# pr0board.net
KiCad netlist of a schematic drawn in EAGLE
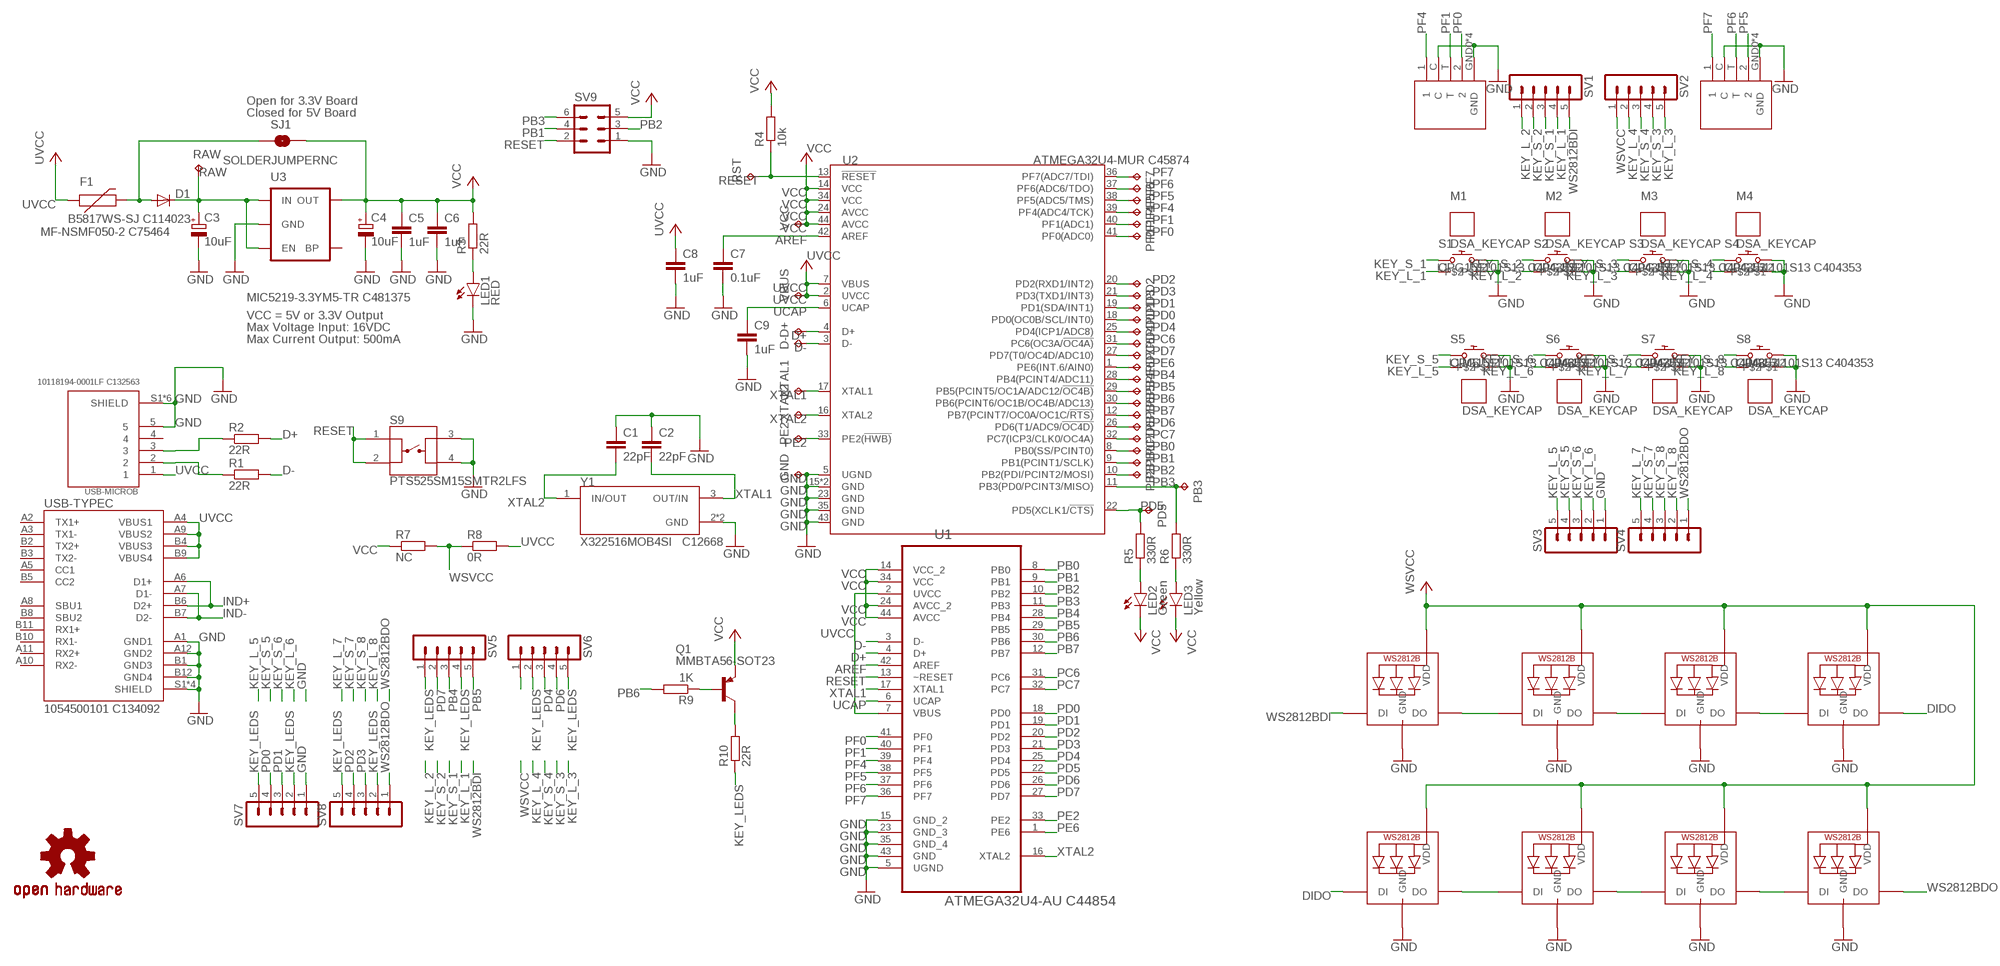
[diagram p0: schematic, sheet 1]

(export (version "E")
  (design (tool "Eeschema 10.0.6"))
  (components
    (comp (ref "C1")
      (value "22pF")
      (footprint "eagle-import:C0603")
      (libsource (lib "eagle-import") (part "C-EUC0603"))
    )
    (comp (ref "C2")
      (value "22pF")
      (footprint "eagle-import:C0603")
      (libsource (lib "eagle-import") (part "C-EUC0603"))
    )
    (comp (ref "C3")
      (value "10uF")
      (footprint "eagle-import:CT3216")
      (libsource (lib "eagle-import") (part "CPOL-EUCT3216"))
    )
    (comp (ref "C4")
      (value "10uF")
      (footprint "eagle-import:CT3216")
      (libsource (lib "eagle-import") (part "CPOL-EUCT3216"))
    )
    (comp (ref "C5")
      (value "1uF")
      (footprint "eagle-import:C0603")
      (libsource (lib "eagle-import") (part "C-EUC0603"))
    )
    (comp (ref "C6")
      (value "1uF")
      (footprint "eagle-import:C0603")
      (libsource (lib "eagle-import") (part "C-EUC0603"))
    )
    (comp (ref "C7")
      (value "0.1uF")
      (footprint "eagle-import:C0603")
      (libsource (lib "eagle-import") (part "C-EUC0603"))
    )
    (comp (ref "C8")
      (value "1uF")
      (footprint "eagle-import:C0603")
      (libsource (lib "eagle-import") (part "C-EUC0603"))
    )
    (comp (ref "C9")
      (value "1uF")
      (footprint "eagle-import:C0603")
      (libsource (lib "eagle-import") (part "C-EUC0603"))
    )
    (comp (ref "D+")
      (value "TPB1,27")
      (footprint "eagle-import:B1,27")
      (libsource (lib "eagle-import") (part "TPB1,27"))
    )
    (comp (ref "D-")
      (value "TPB1,27")
      (footprint "eagle-import:B1,27")
      (libsource (lib "eagle-import") (part "TPB1,27"))
    )
    (comp (ref "D1")
      (value "B5817WS-SJ C114023")
      (footprint "eagle-import:SOD-323")
      (libsource (lib "eagle-import") (part "DIODESOD"))
    )
    (comp (ref "F1")
      (value "MF-NSMF050-2 C75464")
      (footprint "eagle-import:PTC-1206")
      (libsource (lib "eagle-import") (part "PTCSMD"))
    )
    (comp (ref "GND")
      (value "TPB1,27")
      (footprint "eagle-import:B1,27")
      (libsource (lib "eagle-import") (part "TPB1,27"))
    )
    (comp (ref "LED1")
      (value "RED")
      (footprint "eagle-import:CHIP-LED0603")
      (libsource (lib "eagle-import") (part "LEDCHIP-LED0603"))
    )
    (comp (ref "LED2")
      (value "Green")
      (footprint "eagle-import:CHIP-LED0603")
      (libsource (lib "eagle-import") (part "LEDCHIP-LED0603"))
    )
    (comp (ref "LED3")
      (value "Yellow")
      (footprint "eagle-import:CHIP-LED0603")
      (libsource (lib "eagle-import") (part "LEDCHIP-LED0603"))
    )
    (comp (ref "LED4")
      (value "WS2812B3535")
      (footprint "eagle-import:LED3535")
      (libsource (lib "eagle-import") (part "WS2812B3535"))
    )
    (comp (ref "LED5")
      (value "WS2812B3535")
      (footprint "eagle-import:LED3535")
      (libsource (lib "eagle-import") (part "WS2812B3535"))
    )
    (comp (ref "LED6")
      (value "WS2812B3535")
      (footprint "eagle-import:LED3535")
      (libsource (lib "eagle-import") (part "WS2812B3535"))
    )
    (comp (ref "LED7")
      (value "WS2812B3535")
      (footprint "eagle-import:LED3535")
      (libsource (lib "eagle-import") (part "WS2812B3535"))
    )
    (comp (ref "LED8")
      (value "WS2812B3535")
      (footprint "eagle-import:LED3535")
      (libsource (lib "eagle-import") (part "WS2812B3535"))
    )
    (comp (ref "LED9")
      (value "WS2812B3535")
      (footprint "eagle-import:LED3535")
      (libsource (lib "eagle-import") (part "WS2812B3535"))
    )
    (comp (ref "LED10")
      (value "WS2812B3535")
      (footprint "eagle-import:LED3535")
      (libsource (lib "eagle-import") (part "WS2812B3535"))
    )
    (comp (ref "LED11")
      (value "WS2812B3535")
      (footprint "eagle-import:LED3535")
      (libsource (lib "eagle-import") (part "WS2812B3535"))
    )
    (comp (ref "M1")
      (value "DSA_KEYCAP")
      (footprint "eagle-import:DSA_KEYCAP")
      (libsource (lib "eagle-import") (part "DSA_KEYCAP"))
    )
    (comp (ref "M2")
      (value "DSA_KEYCAP")
      (footprint "eagle-import:DSA_KEYCAP")
      (libsource (lib "eagle-import") (part "DSA_KEYCAP"))
    )
    (comp (ref "M3")
      (value "DSA_KEYCAP")
      (footprint "eagle-import:DSA_KEYCAP")
      (libsource (lib "eagle-import") (part "DSA_KEYCAP"))
    )
    (comp (ref "M4")
      (value "DSA_KEYCAP")
      (footprint "eagle-import:DSA_KEYCAP")
      (libsource (lib "eagle-import") (part "DSA_KEYCAP"))
    )
    (comp (ref "M5")
      (value "DSA_KEYCAP")
      (footprint "eagle-import:DSA_KEYCAP")
      (libsource (lib "eagle-import") (part "DSA_KEYCAP"))
    )
    (comp (ref "M6")
      (value "DSA_KEYCAP")
      (footprint "eagle-import:DSA_KEYCAP")
      (libsource (lib "eagle-import") (part "DSA_KEYCAP"))
    )
    (comp (ref "M7")
      (value "DSA_KEYCAP")
      (footprint "eagle-import:DSA_KEYCAP")
      (libsource (lib "eagle-import") (part "DSA_KEYCAP"))
    )
    (comp (ref "M8")
      (value "DSA_KEYCAP")
      (footprint "eagle-import:DSA_KEYCAP")
      (libsource (lib "eagle-import") (part "DSA_KEYCAP"))
    )
    (comp (ref "PB0")
      (value "TPB1,27")
      (footprint "eagle-import:B1,27")
      (libsource (lib "eagle-import") (part "TPB1,27"))
    )
    (comp (ref "PB1")
      (value "TPB1,27")
      (footprint "eagle-import:B1,27")
      (libsource (lib "eagle-import") (part "TPB1,27"))
    )
    (comp (ref "PB2")
      (value "TPB1,27")
      (footprint "eagle-import:B1,27")
      (libsource (lib "eagle-import") (part "TPB1,27"))
    )
    (comp (ref "PB3")
      (value "TPB1,27")
      (footprint "eagle-import:B1,27")
      (libsource (lib "eagle-import") (part "TPB1,27"))
    )
    (comp (ref "PB4")
      (value "TPB1,27")
      (footprint "eagle-import:B1,27")
      (libsource (lib "eagle-import") (part "TPB1,27"))
    )
    (comp (ref "PB5")
      (value "TPB1,27")
      (footprint "eagle-import:B1,27")
      (libsource (lib "eagle-import") (part "TPB1,27"))
    )
    (comp (ref "PB6")
      (value "TPB1,27")
      (footprint "eagle-import:B1,27")
      (libsource (lib "eagle-import") (part "TPB1,27"))
    )
    (comp (ref "PB7")
      (value "TPB1,27")
      (footprint "eagle-import:B1,27")
      (libsource (lib "eagle-import") (part "TPB1,27"))
    )
    (comp (ref "PC6")
      (value "TPB1,27")
      (footprint "eagle-import:B1,27")
      (libsource (lib "eagle-import") (part "TPB1,27"))
    )
    (comp (ref "PC7")
      (value "TPB1,27")
      (footprint "eagle-import:B1,27")
      (libsource (lib "eagle-import") (part "TPB1,27"))
    )
    (comp (ref "PD0")
      (value "TPB1,27")
      (footprint "eagle-import:B1,27")
      (libsource (lib "eagle-import") (part "TPB1,27"))
    )
    (comp (ref "PD1")
      (value "TPB1,27")
      (footprint "eagle-import:B1,27")
      (libsource (lib "eagle-import") (part "TPB1,27"))
    )
    (comp (ref "PD2")
      (value "TPB1,27")
      (footprint "eagle-import:B1,27")
      (libsource (lib "eagle-import") (part "TPB1,27"))
    )
    (comp (ref "PD3")
      (value "TPB1,27")
      (footprint "eagle-import:B1,27")
      (libsource (lib "eagle-import") (part "TPB1,27"))
    )
    (comp (ref "PD4")
      (value "TPB1,27")
      (footprint "eagle-import:B1,27")
      (libsource (lib "eagle-import") (part "TPB1,27"))
    )
    (comp (ref "PD5")
      (value "TPB1,27")
      (footprint "eagle-import:B1,27")
      (libsource (lib "eagle-import") (part "TPB1,27"))
    )
    (comp (ref "PD6")
      (value "TPB1,27")
      (footprint "eagle-import:B1,27")
      (libsource (lib "eagle-import") (part "TPB1,27"))
    )
    (comp (ref "PD7")
      (value "TPB1,27")
      (footprint "eagle-import:B1,27")
      (libsource (lib "eagle-import") (part "TPB1,27"))
    )
    (comp (ref "PE2")
      (value "TPB1,27")
      (footprint "eagle-import:B1,27")
      (libsource (lib "eagle-import") (part "TPB1,27"))
    )
    (comp (ref "PE6")
      (value "TPB1,27")
      (footprint "eagle-import:B1,27")
      (libsource (lib "eagle-import") (part "TPB1,27"))
    )
    (comp (ref "PF0")
      (value "TPB1,27")
      (footprint "eagle-import:B1,27")
      (libsource (lib "eagle-import") (part "TPB1,27"))
    )
    (comp (ref "PF1")
      (value "TPB1,27")
      (footprint "eagle-import:B1,27")
      (libsource (lib "eagle-import") (part "TPB1,27"))
    )
    (comp (ref "PF4")
      (value "TPB1,27")
      (footprint "eagle-import:B1,27")
      (libsource (lib "eagle-import") (part "TPB1,27"))
    )
    (comp (ref "PF5")
      (value "TPB1,27")
      (footprint "eagle-import:B1,27")
      (libsource (lib "eagle-import") (part "TPB1,27"))
    )
    (comp (ref "PF6")
      (value "TPB1,27")
      (footprint "eagle-import:B1,27")
      (libsource (lib "eagle-import") (part "TPB1,27"))
    )
    (comp (ref "PF7")
      (value "TPB1,27")
      (footprint "eagle-import:B1,27")
      (libsource (lib "eagle-import") (part "TPB1,27"))
    )
    (comp (ref "Q1")
      (value "MMBTA56-SOT23")
      (footprint "eagle-import:SOT23")
      (libsource (lib "eagle-import") (part "-?SOT23MMBTA56"))
    )
    (comp (ref "R1")
      (value "22R")
      (footprint "eagle-import:R0603")
      (libsource (lib "eagle-import") (part "resistor_348_R-EU_R0603"))
    )
    (comp (ref "R2")
      (value "22R")
      (footprint "eagle-import:R0603")
      (libsource (lib "eagle-import") (part "resistor_348_R-EU_R0603"))
    )
    (comp (ref "R3")
      (value "22R")
      (footprint "eagle-import:R0603")
      (libsource (lib "eagle-import") (part "resistor_348_R-EU_R0603"))
    )
    (comp (ref "R4")
      (value "10k")
      (footprint "eagle-import:R0603")
      (libsource (lib "eagle-import") (part "resistor_348_R-EU_R0603"))
    )
    (comp (ref "R5")
      (value "330R")
      (footprint "eagle-import:R0603")
      (libsource (lib "eagle-import") (part "resistor_348_R-EU_R0603"))
    )
    (comp (ref "R6")
      (value "330R")
      (footprint "eagle-import:R0603")
      (libsource (lib "eagle-import") (part "resistor_348_R-EU_R0603"))
    )
    (comp (ref "R7")
      (value "NC")
      (footprint "eagle-import:R0603")
      (libsource (lib "eagle-import") (part "resistor_348_R-EU_R0603"))
    )
    (comp (ref "R8")
      (value "0R")
      (footprint "eagle-import:R0603")
      (libsource (lib "eagle-import") (part "resistor_348_R-EU_R0603"))
    )
    (comp (ref "R9")
      (value "1K")
      (footprint "eagle-import:R0603")
      (libsource (lib "eagle-import") (part "R-EU_R0603"))
    )
    (comp (ref "R10")
      (value "22R")
      (footprint "eagle-import:R0805")
      (libsource (lib "eagle-import") (part "R-EU_R0805"))
    )
    (comp (ref "RAW")
      (value "TPB1,27")
      (footprint "eagle-import:B1,27")
      (libsource (lib "eagle-import") (part "TPB1,27"))
    )
    (comp (ref "RST")
      (value "TPB1,27")
      (footprint "eagle-import:B1,27")
      (libsource (lib "eagle-import") (part "TPB1,27"))
    )
    (comp (ref "S1")
      (value "CPG151101S13 C404353")
      (footprint "eagle-import:CHERRY_MX_LED")
      (libsource (lib "eagle-import") (part "CHERRY_MX_LED"))
    )
    (comp (ref "S2")
      (value "CPG151101S13 C404353")
      (footprint "eagle-import:CHERRY_MX_LED")
      (libsource (lib "eagle-import") (part "CHERRY_MX_LED"))
    )
    (comp (ref "S3")
      (value "CPG151101S13 C404353")
      (footprint "eagle-import:CHERRY_MX_LED")
      (libsource (lib "eagle-import") (part "CHERRY_MX_LED"))
    )
    (comp (ref "S4")
      (value "CPG151101S13 C404353")
      (footprint "eagle-import:CHERRY_MX_LED")
      (libsource (lib "eagle-import") (part "CHERRY_MX_LED"))
    )
    (comp (ref "S5")
      (value "CPG151101S13 C404353")
      (footprint "eagle-import:CHERRY_MX_LED")
      (libsource (lib "eagle-import") (part "CHERRY_MX_LED"))
    )
    (comp (ref "S6")
      (value "CPG151101S13 C404353")
      (footprint "eagle-import:CHERRY_MX_LED")
      (libsource (lib "eagle-import") (part "CHERRY_MX_LED"))
    )
    (comp (ref "S7")
      (value "CPG151101S13 C404353")
      (footprint "eagle-import:CHERRY_MX_LED")
      (libsource (lib "eagle-import") (part "CHERRY_MX_LED"))
    )
    (comp (ref "S8")
      (value "CPG151101S13 C404353")
      (footprint "eagle-import:CHERRY_MX_LED")
      (libsource (lib "eagle-import") (part "CHERRY_MX_LED"))
    )
    (comp (ref "S9")
      (value "PTS525SM15SMTR2LFS")
      (footprint "eagle-import:SW_PTS525SM15SMTR2LFS")
      (fields (field (name "MF") "C&K"))
      (libsource (lib "eagle-import") (part "PTS525SM15SMTR2LFS"))
    )
    (comp (ref "SJ1")
      (value "SOLDERJUMPERNC")
      (footprint "eagle-import:SJ_2S")
      (libsource (lib "eagle-import") (part "SOLDERJUMPERNC"))
    )
    (comp (ref "SV1")
      (value "MA05-1")
      (footprint "eagle-import:MA05-1")
      (libsource (lib "eagle-import") (part "MA05-1"))
    )
    (comp (ref "SV2")
      (value "MA05-1")
      (footprint "eagle-import:MA05-1")
      (libsource (lib "eagle-import") (part "MA05-1"))
    )
    (comp (ref "SV3")
      (value "MA05-1")
      (footprint "eagle-import:MA05-1")
      (libsource (lib "eagle-import") (part "MA05-1"))
    )
    (comp (ref "SV4")
      (value "MA05-1")
      (footprint "eagle-import:MA05-1")
      (libsource (lib "eagle-import") (part "MA05-1"))
    )
    (comp (ref "SV5")
      (value "MA05-1")
      (footprint "eagle-import:MA05-1")
      (libsource (lib "eagle-import") (part "MA05-1"))
    )
    (comp (ref "SV6")
      (value "MA05-1")
      (footprint "eagle-import:MA05-1")
      (libsource (lib "eagle-import") (part "MA05-1"))
    )
    (comp (ref "SV7")
      (value "MA05-1")
      (footprint "eagle-import:MA05-1")
      (libsource (lib "eagle-import") (part "MA05-1"))
    )
    (comp (ref "SV8")
      (value "MA05-1")
      (footprint "eagle-import:MA05-1")
      (libsource (lib "eagle-import") (part "MA05-1"))
    )
    (comp (ref "SV9")
      (value "MA03-2")
      (footprint "eagle-import:MA03-2")
      (libsource (lib "eagle-import") (part "MA03-2"))
    )
    (comp (ref "U$1")
      (value "OSHW-LOGOS")
      (footprint "eagle-import:OSHW-LOGO-S")
      (libsource (lib "eagle-import") (part "OSHW-LOGOS"))
    )
    (comp (ref "U$2")
      (value "TM-2024A")
      (footprint "eagle-import:TM-2024A")
      (libsource (lib "eagle-import") (part "TM-2024A"))
    )
    (comp (ref "U$3")
      (value "TM-2024A")
      (footprint "eagle-import:TM-2024A")
      (libsource (lib "eagle-import") (part "TM-2024A"))
    )
    (comp (ref "U1")
      (value "ATMEGA32U4-AU C44854")
      (footprint "eagle-import:QFP80P1200X1200X120-44N")
      (fields (field (name "MF") "Microchip Technology") (field (name "MP") "ATMEGA32U4-AU"))
      (libsource (lib "eagle-import") (part "ATMEGA32U4-AU"))
    )
    (comp (ref "U2")
      (value "ATMEGA32U4-MUR C45874")
      (footprint "eagle-import:QFN44G-0.5-7X7MM")
      (fields (field (name "MF") "Microchip") (field (name "MP") "ATMEGA32U4-MUR"))
      (libsource (lib "eagle-import") (part "MCU-ATMEGA32U4-MUR(VQFN44)"))
    )
    (comp (ref "U3")
      (value "MIC5219-3.3YM5-TR C481375")
      (footprint "eagle-import:SC70")
      (libsource (lib "eagle-import") (part "V_REG_LDOSMD2"))
    )
    (comp (ref "USB-MICROB")
      (value "10118194-0001LF C132563")
      (footprint "eagle-import:AMPHENOL_10118194-0001LF")
      (fields (field (name "MF") "Amphenol ICC (FCI)") (field (name "MP") "10118194-0001LF"))
      (libsource (lib "eagle-import") (part "10118194-0001LF"))
    )
    (comp (ref "USB-TYPEC")
      (value "1054500101 C134092")
      (footprint "eagle-import:MOLEX_105450-0101")
      (fields (field (name "MF") "Molex") (field (name "MP") "1054500101"))
      (libsource (lib "eagle-import") (part "105450-0101"))
    )
    (comp (ref "VBUS")
      (value "TPB1,27")
      (footprint "eagle-import:B1,27")
      (libsource (lib "eagle-import") (part "TPB1,27"))
    )
    (comp (ref "VCC")
      (value "TPB1,27")
      (footprint "eagle-import:B1,27")
      (libsource (lib "eagle-import") (part "TPB1,27"))
    )
    (comp (ref "XTAL1")
      (value "TPB1,27")
      (footprint "eagle-import:B1,27")
      (libsource (lib "eagle-import") (part "TPB1,27"))
    )
    (comp (ref "XTAL2")
      (value "TPB1,27")
      (footprint "eagle-import:B1,27")
      (libsource (lib "eagle-import") (part "TPB1,27"))
    )
    (comp (ref "Y1")
      (value "X322516MOB4SI C12668")
      (footprint "eagle-import:XTAL_ECS-160-18-33Q-DS")
      (fields (field (name "MF") "ECS Inc.") (field (name "MP") "ECS-160-18-33Q-DS"))
      (libsource (lib "eagle-import") (part "ECS-160-18-33Q-DS"))
    )
  )
  (nets
    (net (code "1") (name "/AREF") (class "Default")
      (node (ref "C7") (pin "1") (pinfunction "1_1") (pintype "passive"))
      (node (ref "U1") (pin "42") (pinfunction "AREF_42") (pintype "input"))
      (node (ref "U2") (pin "42") (pinfunction "AREF_42") (pintype "bidirectional"))
    )
    (net (code "2") (name "/D+") (class "Default")
      (node (ref "D+") (pin "TP") (pinfunction "TP_TP") (pintype "input"))
      (node (ref "R2") (pin "2") (pinfunction "2_2") (pintype "passive"))
      (node (ref "U1") (pin "4") (pinfunction "D+_4") (pintype "passive"))
      (node (ref "U2") (pin "4") (pinfunction "D+_4") (pintype "bidirectional"))
    )
    (net (code "3") (name "/D-") (class "Default")
      (node (ref "D-") (pin "TP") (pinfunction "TP_TP") (pintype "input"))
      (node (ref "R1") (pin "2") (pinfunction "2_2") (pintype "passive"))
      (node (ref "U1") (pin "3") (pinfunction "D-_3") (pintype "passive"))
      (node (ref "U2") (pin "3") (pinfunction "D-_3") (pintype "bidirectional"))
    )
    (net (code "4") (name "/DIDO") (class "Default")
      (node (ref "LED7") (pin "3") (pinfunction "DO_3") (pintype "output"))
      (node (ref "LED8") (pin "1") (pinfunction "DI_1") (pintype "input"))
    )
    (net (code "5") (name "/IND+") (class "Default")
      (node (ref "R2") (pin "1") (pinfunction "1_1") (pintype "passive"))
      (node (ref "USB-MICROB") (pin "3") (pinfunction "3_3") (pintype "passive"))
      (node (ref "USB-TYPEC") (pin "A6") (pinfunction "D1+_A6") (pintype "passive"))
      (node (ref "USB-TYPEC") (pin "B6") (pinfunction "D2+_B6") (pintype "passive"))
    )
    (net (code "6") (name "/IND-") (class "Default")
      (node (ref "R1") (pin "1") (pinfunction "1_1") (pintype "passive"))
      (node (ref "USB-MICROB") (pin "2") (pinfunction "2_2") (pintype "passive"))
      (node (ref "USB-TYPEC") (pin "A7") (pinfunction "D1-_A7") (pintype "passive"))
      (node (ref "USB-TYPEC") (pin "B7") (pinfunction "D2-_B7") (pintype "passive"))
    )
    (net (code "7") (name "/KEY_LEDS") (class "Default")
      (node (ref "R10") (pin "1") (pinfunction "1_1") (pintype "passive"))
      (node (ref "SV5") (pin "1") (pinfunction "1_1") (pintype "passive"))
      (node (ref "SV5") (pin "4") (pinfunction "4_4") (pintype "passive"))
      (node (ref "SV6") (pin "2") (pinfunction "2_2") (pintype "passive"))
      (node (ref "SV6") (pin "5") (pinfunction "5_5") (pintype "passive"))
      (node (ref "SV7") (pin "2") (pinfunction "2_2") (pintype "passive"))
      (node (ref "SV7") (pin "5") (pinfunction "5_5") (pintype "passive"))
      (node (ref "SV8") (pin "2") (pinfunction "2_2") (pintype "passive"))
      (node (ref "SV8") (pin "5") (pinfunction "5_5") (pintype "passive"))
    )
    (net (code "8") (name "/KEY_L_1") (class "Default")
      (node (ref "S1") (pin "L1") (pinfunction "P$1_L1") (pintype "bidirectional"))
      (node (ref "SV1") (pin "4") (pinfunction "4_4") (pintype "passive"))
    )
    (net (code "9") (name "/KEY_L_2") (class "Default")
      (node (ref "S2") (pin "L1") (pinfunction "P$1_L1") (pintype "bidirectional"))
      (node (ref "SV1") (pin "1") (pinfunction "1_1") (pintype "passive"))
    )
    (net (code "10") (name "/KEY_L_3") (class "Default")
      (node (ref "S3") (pin "L1") (pinfunction "P$1_L1") (pintype "bidirectional"))
      (node (ref "SV2") (pin "5") (pinfunction "5_5") (pintype "passive"))
    )
    (net (code "11") (name "/KEY_L_4") (class "Default")
      (node (ref "S4") (pin "L1") (pinfunction "P$1_L1") (pintype "bidirectional"))
      (node (ref "SV2") (pin "2") (pinfunction "2_2") (pintype "passive"))
    )
    (net (code "12") (name "/KEY_L_5") (class "Default")
      (node (ref "S5") (pin "L1") (pinfunction "P$1_L1") (pintype "bidirectional"))
      (node (ref "SV3") (pin "5") (pinfunction "5_5") (pintype "passive"))
    )
    (net (code "13") (name "/KEY_L_6") (class "Default")
      (node (ref "S6") (pin "L1") (pinfunction "P$1_L1") (pintype "bidirectional"))
      (node (ref "SV3") (pin "2") (pinfunction "2_2") (pintype "passive"))
    )
    (net (code "14") (name "/KEY_L_7") (class "Default")
      (node (ref "S7") (pin "L1") (pinfunction "P$1_L1") (pintype "bidirectional"))
      (node (ref "SV4") (pin "5") (pinfunction "5_5") (pintype "passive"))
    )
    (net (code "15") (name "/KEY_L_8") (class "Default")
      (node (ref "S8") (pin "L1") (pinfunction "P$1_L1") (pintype "bidirectional"))
      (node (ref "SV4") (pin "2") (pinfunction "2_2") (pintype "passive"))
    )
    (net (code "16") (name "/KEY_S_1") (class "Default")
      (node (ref "S1") (pin "S1") (pinfunction "1_S1") (pintype "passive"))
      (node (ref "SV1") (pin "3") (pinfunction "3_3") (pintype "passive"))
    )
    (net (code "17") (name "/KEY_S_2") (class "Default")
      (node (ref "S2") (pin "S1") (pinfunction "1_S1") (pintype "passive"))
      (node (ref "SV1") (pin "2") (pinfunction "2_2") (pintype "passive"))
    )
    (net (code "18") (name "/KEY_S_3") (class "Default")
      (node (ref "S3") (pin "S1") (pinfunction "1_S1") (pintype "passive"))
      (node (ref "SV2") (pin "4") (pinfunction "4_4") (pintype "passive"))
    )
    (net (code "19") (name "/KEY_S_4") (class "Default")
      (node (ref "S4") (pin "S1") (pinfunction "1_S1") (pintype "passive"))
      (node (ref "SV2") (pin "3") (pinfunction "3_3") (pintype "passive"))
    )
    (net (code "20") (name "/KEY_S_5") (class "Default")
      (node (ref "S5") (pin "S1") (pinfunction "1_S1") (pintype "passive"))
      (node (ref "SV3") (pin "4") (pinfunction "4_4") (pintype "passive"))
    )
    (net (code "21") (name "/KEY_S_6") (class "Default")
      (node (ref "S6") (pin "S1") (pinfunction "1_S1") (pintype "passive"))
      (node (ref "SV3") (pin "3") (pinfunction "3_3") (pintype "passive"))
    )
    (net (code "22") (name "/KEY_S_7") (class "Default")
      (node (ref "S7") (pin "S1") (pinfunction "1_S1") (pintype "passive"))
      (node (ref "SV4") (pin "4") (pinfunction "4_4") (pintype "passive"))
    )
    (net (code "23") (name "/KEY_S_8") (class "Default")
      (node (ref "S8") (pin "S1") (pinfunction "1_S1") (pintype "passive"))
      (node (ref "SV4") (pin "3") (pinfunction "3_3") (pintype "passive"))
    )
    (net (code "24") (name "/PB0") (class "Default")
      (node (ref "PB0") (pin "TP") (pinfunction "TP_TP") (pintype "input"))
      (node (ref "U1") (pin "8") (pinfunction "PB0_8") (pintype "bidirectional"))
      (node (ref "U2") (pin "8") (pinfunction "PB0(SS/PCINT0)_8") (pintype "bidirectional"))
    )
    (net (code "25") (name "/PB1") (class "Default")
      (node (ref "PB1") (pin "TP") (pinfunction "TP_TP") (pintype "input"))
      (node (ref "SV9") (pin "4") (pinfunction "4_4") (pintype "passive"))
      (node (ref "U1") (pin "9") (pinfunction "PB1_9") (pintype "bidirectional"))
      (node (ref "U2") (pin "9") (pinfunction "PB1(PCINT1/SCLK)_9") (pintype "bidirectional"))
    )
    (net (code "26") (name "/PB2") (class "Default")
      (node (ref "PB2") (pin "TP") (pinfunction "TP_TP") (pintype "input"))
      (node (ref "SV9") (pin "3") (pinfunction "3_3") (pintype "passive"))
      (node (ref "U1") (pin "10") (pinfunction "PB2_10") (pintype "bidirectional"))
      (node (ref "U2") (pin "10") (pinfunction "PB2(PDI/PCINT2/MOSI)_10") (pintype "bidirectional"))
    )
    (net (code "27") (name "/PB3") (class "Default")
      (node (ref "PB3") (pin "TP") (pinfunction "TP_TP") (pintype "input"))
      (node (ref "R6") (pin "2") (pinfunction "2_2") (pintype "passive"))
      (node (ref "SV9") (pin "6") (pinfunction "6_6") (pintype "passive"))
      (node (ref "U1") (pin "11") (pinfunction "PB3_11") (pintype "bidirectional"))
      (node (ref "U2") (pin "11") (pinfunction "PB3(PD0/PCINT3/MISO)_11") (pintype "bidirectional"))
    )
    (net (code "28") (name "/PB4") (class "Default")
      (node (ref "PB4") (pin "TP") (pinfunction "TP_TP") (pintype "input"))
      (node (ref "SV5") (pin "3") (pinfunction "3_3") (pintype "passive"))
      (node (ref "U1") (pin "28") (pinfunction "PB4_28") (pintype "bidirectional"))
      (node (ref "U2") (pin "28") (pinfunction "PB4(PCINT4/ADC11)_28") (pintype "bidirectional"))
    )
    (net (code "29") (name "/PB5") (class "Default")
      (node (ref "PB5") (pin "TP") (pinfunction "TP_TP") (pintype "input"))
      (node (ref "SV5") (pin "5") (pinfunction "5_5") (pintype "passive"))
      (node (ref "U1") (pin "29") (pinfunction "PB5_29") (pintype "bidirectional"))
      (node (ref "U2") (pin "29") (pinfunction "PB5(PCINT5/OC1A/ADC12/~{OC4B})_29") (pintype "bidirectional"))
    )
    (net (code "30") (name "/PB6") (class "Default")
      (node (ref "PB6") (pin "TP") (pinfunction "TP_TP") (pintype "input"))
      (node (ref "R9") (pin "2") (pinfunction "2_2") (pintype "passive"))
      (node (ref "U1") (pin "30") (pinfunction "PB6_30") (pintype "bidirectional"))
      (node (ref "U2") (pin "30") (pinfunction "PB6(PCINT6/OC1B/OC4B/ADC13)_30") (pintype "bidirectional"))
    )
    (net (code "31") (name "/PB7") (class "Default")
      (node (ref "PB7") (pin "TP") (pinfunction "TP_TP") (pintype "input"))
      (node (ref "U1") (pin "12") (pinfunction "PB7_12") (pintype "bidirectional"))
      (node (ref "U2") (pin "12") (pinfunction "PB7(PCINT7/OC0A/OC1C/~{RTS})_12") (pintype "bidirectional"))
    )
    (net (code "32") (name "/PC6") (class "Default")
      (node (ref "PC6") (pin "TP") (pinfunction "TP_TP") (pintype "input"))
      (node (ref "U1") (pin "31") (pinfunction "PC6_31") (pintype "bidirectional"))
      (node (ref "U2") (pin "31") (pinfunction "PC6(OC3A/~{OC4A})_31") (pintype "bidirectional"))
    )
    (net (code "33") (name "/PC7") (class "Default")
      (node (ref "PC7") (pin "TP") (pinfunction "TP_TP") (pintype "input"))
      (node (ref "U1") (pin "32") (pinfunction "PC7_32") (pintype "bidirectional"))
      (node (ref "U2") (pin "32") (pinfunction "PC7(ICP3/CLK0/OC4A)_32") (pintype "bidirectional"))
    )
    (net (code "34") (name "/PD0") (class "Default")
      (node (ref "PD0") (pin "TP") (pinfunction "TP_TP") (pintype "input"))
      (node (ref "SV7") (pin "4") (pinfunction "4_4") (pintype "passive"))
      (node (ref "U1") (pin "18") (pinfunction "PD0_18") (pintype "bidirectional"))
      (node (ref "U2") (pin "18") (pinfunction "PD0(OC0B/SCL/INT0)_18") (pintype "bidirectional"))
    )
    (net (code "35") (name "/PD1") (class "Default")
      (node (ref "PD1") (pin "TP") (pinfunction "TP_TP") (pintype "input"))
      (node (ref "SV7") (pin "3") (pinfunction "3_3") (pintype "passive"))
      (node (ref "U1") (pin "19") (pinfunction "PD1_19") (pintype "bidirectional"))
      (node (ref "U2") (pin "19") (pinfunction "PD1(SDA/INT1)_19") (pintype "bidirectional"))
    )
    (net (code "36") (name "/PD2") (class "Default")
      (node (ref "PD2") (pin "TP") (pinfunction "TP_TP") (pintype "input"))
      (node (ref "SV8") (pin "4") (pinfunction "4_4") (pintype "passive"))
      (node (ref "U1") (pin "20") (pinfunction "PD2_20") (pintype "bidirectional"))
      (node (ref "U2") (pin "20") (pinfunction "PD2(RXD1/INT2)_20") (pintype "bidirectional"))
    )
    (net (code "37") (name "/PD3") (class "Default")
      (node (ref "PD3") (pin "TP") (pinfunction "TP_TP") (pintype "input"))
      (node (ref "SV8") (pin "3") (pinfunction "3_3") (pintype "passive"))
      (node (ref "U1") (pin "21") (pinfunction "PD3_21") (pintype "bidirectional"))
      (node (ref "U2") (pin "21") (pinfunction "PD3(TXD1/INT3)_21") (pintype "bidirectional"))
    )
    (net (code "38") (name "/PD4") (class "Default")
      (node (ref "PD4") (pin "TP") (pinfunction "TP_TP") (pintype "input"))
      (node (ref "SV6") (pin "3") (pinfunction "3_3") (pintype "passive"))
      (node (ref "U1") (pin "25") (pinfunction "PD4_25") (pintype "bidirectional"))
      (node (ref "U2") (pin "25") (pinfunction "PD4(ICP1/ADC8)_25") (pintype "bidirectional"))
    )
    (net (code "39") (name "/PD5") (class "Default")
      (node (ref "PD5") (pin "TP") (pinfunction "TP_TP") (pintype "input"))
      (node (ref "R5") (pin "2") (pinfunction "2_2") (pintype "passive"))
      (node (ref "U1") (pin "22") (pinfunction "PD5_22") (pintype "bidirectional"))
      (node (ref "U2") (pin "22") (pinfunction "PD5(XCLK1/~{CTS})_22") (pintype "bidirectional"))
    )
    (net (code "40") (name "/PD6") (class "Default")
      (node (ref "PD6") (pin "TP") (pinfunction "TP_TP") (pintype "input"))
      (node (ref "SV6") (pin "4") (pinfunction "4_4") (pintype "passive"))
      (node (ref "U1") (pin "26") (pinfunction "PD6_26") (pintype "bidirectional"))
      (node (ref "U2") (pin "26") (pinfunction "PD6(T1/ADC9/~{OC4D})_26") (pintype "bidirectional"))
    )
    (net (code "41") (name "/PD7") (class "Default")
      (node (ref "PD7") (pin "TP") (pinfunction "TP_TP") (pintype "input"))
      (node (ref "SV5") (pin "2") (pinfunction "2_2") (pintype "passive"))
      (node (ref "U1") (pin "27") (pinfunction "PD7_27") (pintype "bidirectional"))
      (node (ref "U2") (pin "27") (pinfunction "PD7(T0/OC4D/ADC10)_27") (pintype "bidirectional"))
    )
    (net (code "42") (name "/PE2") (class "Default")
      (node (ref "PE2") (pin "TP") (pinfunction "TP_TP") (pintype "input"))
      (node (ref "U1") (pin "33") (pinfunction "PE2_33") (pintype "bidirectional"))
      (node (ref "U2") (pin "33") (pinfunction "PE2(~{HWB})_33") (pintype "bidirectional"))
    )
    (net (code "43") (name "/PE6") (class "Default")
      (node (ref "PE6") (pin "TP") (pinfunction "TP_TP") (pintype "input"))
      (node (ref "U1") (pin "1") (pinfunction "PE6_1") (pintype "bidirectional"))
      (node (ref "U2") (pin "1") (pinfunction "PE6(INT.6/AIN0)_1") (pintype "bidirectional"))
    )
    (net (code "44") (name "/PF0") (class "Default")
      (node (ref "PF0") (pin "TP") (pinfunction "TP_TP") (pintype "input"))
      (node (ref "U$2") (pin "2") (pinfunction "2_2") (pintype "bidirectional"))
      (node (ref "U1") (pin "41") (pinfunction "PF0_41") (pintype "bidirectional"))
      (node (ref "U2") (pin "41") (pinfunction "PF0(ADC0)_41") (pintype "bidirectional"))
    )
    (net (code "45") (name "/PF1") (class "Default")
      (node (ref "PF1") (pin "TP") (pinfunction "TP_TP") (pintype "input"))
      (node (ref "U$2") (pin "T") (pinfunction "T_T") (pintype "bidirectional"))
      (node (ref "U1") (pin "40") (pinfunction "PF1_40") (pintype "bidirectional"))
      (node (ref "U2") (pin "40") (pinfunction "PF1(ADC1)_40") (pintype "bidirectional"))
    )
    (net (code "46") (name "/PF4") (class "Default")
      (node (ref "PF4") (pin "TP") (pinfunction "TP_TP") (pintype "input"))
      (node (ref "U$2") (pin "1") (pinfunction "1_1") (pintype "bidirectional"))
      (node (ref "U1") (pin "39") (pinfunction "PF4_39") (pintype "bidirectional"))
      (node (ref "U2") (pin "39") (pinfunction "PF4(ADC4/TCK)_39") (pintype "bidirectional"))
    )
    (net (code "47") (name "/PF5") (class "Default")
      (node (ref "PF5") (pin "TP") (pinfunction "TP_TP") (pintype "input"))
      (node (ref "U$3") (pin "2") (pinfunction "2_2") (pintype "bidirectional"))
      (node (ref "U1") (pin "38") (pinfunction "PF5_38") (pintype "bidirectional"))
      (node (ref "U2") (pin "38") (pinfunction "PF5(ADC5/TMS)_38") (pintype "bidirectional"))
    )
    (net (code "48") (name "/PF6") (class "Default")
      (node (ref "PF6") (pin "TP") (pinfunction "TP_TP") (pintype "input"))
      (node (ref "U$3") (pin "T") (pinfunction "T_T") (pintype "bidirectional"))
      (node (ref "U1") (pin "37") (pinfunction "PF6_37") (pintype "bidirectional"))
      (node (ref "U2") (pin "37") (pinfunction "PF6(ADC6/TDO)_37") (pintype "bidirectional"))
    )
    (net (code "49") (name "/PF7") (class "Default")
      (node (ref "PF7") (pin "TP") (pinfunction "TP_TP") (pintype "input"))
      (node (ref "U$3") (pin "1") (pinfunction "1_1") (pintype "bidirectional"))
      (node (ref "U1") (pin "36") (pinfunction "PF7_36") (pintype "bidirectional"))
      (node (ref "U2") (pin "36") (pinfunction "PF7(ADC7/TDI)_36") (pintype "bidirectional"))
    )
    (net (code "50") (name "/RAW") (class "Default")
      (node (ref "C3") (pin "+") (pinfunction "+_+") (pintype "passive"))
      (node (ref "D1") (pin "1") (pinfunction "C_1") (pintype "passive"))
      (node (ref "RAW") (pin "TP") (pinfunction "TP_TP") (pintype "input"))
      (node (ref "U3") (pin "1") (pinfunction "IN_1") (pintype "input"))
      (node (ref "U3") (pin "3") (pinfunction "EN_3") (pintype "input"))
    )
    (net (code "51") (name "/RESET") (class "Default")
      (node (ref "R4") (pin "1") (pinfunction "1_1") (pintype "passive"))
      (node (ref "RST") (pin "TP") (pinfunction "TP_TP") (pintype "input"))
      (node (ref "S9") (pin "1") (pinfunction "1_1") (pintype "passive"))
      (node (ref "S9") (pin "2") (pinfunction "2_2") (pintype "passive"))
      (node (ref "SV9") (pin "2") (pinfunction "2_2") (pintype "passive"))
      (node (ref "U1") (pin "13") (pinfunction "~{RESET}_13") (pintype "input"))
      (node (ref "U2") (pin "13") (pinfunction "~{RESET}_13") (pintype "bidirectional"))
    )
    (net (code "52") (name "/UCAP") (class "Default")
      (node (ref "C9") (pin "1") (pinfunction "1_1") (pintype "passive"))
      (node (ref "U1") (pin "6") (pinfunction "UCAP_6") (pintype "power_in"))
      (node (ref "U2") (pin "6") (pinfunction "UCAP_6") (pintype "bidirectional"))
    )
    (net (code "53") (name "/WS2812BDI") (class "Default")
      (node (ref "LED4") (pin "1") (pinfunction "DI_1") (pintype "input"))
      (node (ref "SV1") (pin "5") (pinfunction "5_5") (pintype "passive"))
    )
    (net (code "54") (name "/WS2812BDO") (class "Default")
      (node (ref "LED11") (pin "3") (pinfunction "DO_3") (pintype "output"))
      (node (ref "SV4") (pin "1") (pinfunction "1_1") (pintype "passive"))
      (node (ref "SV8") (pin "1") (pinfunction "1_1") (pintype "passive"))
    )
    (net (code "55") (name "/XTAL1") (class "Default")
      (node (ref "C2") (pin "2") (pinfunction "2_2") (pintype "passive"))
      (node (ref "U1") (pin "17") (pinfunction "XTAL1_17") (pintype "input"))
      (node (ref "U2") (pin "17") (pinfunction "XTAL1_17") (pintype "bidirectional"))
      (node (ref "XTAL1") (pin "TP") (pinfunction "TP_TP") (pintype "input"))
      (node (ref "Y1") (pin "3") (pinfunction "OUT/IN_3") (pintype "bidirectional"))
    )
    (net (code "56") (name "/XTAL2") (class "Default")
      (node (ref "C1") (pin "2") (pinfunction "2_2") (pintype "passive"))
      (node (ref "U1") (pin "16") (pinfunction "XTAL2_16") (pintype "output"))
      (node (ref "U2") (pin "16") (pinfunction "XTAL2_16") (pintype "bidirectional"))
      (node (ref "XTAL2") (pin "TP") (pinfunction "TP_TP") (pintype "input"))
      (node (ref "Y1") (pin "1") (pinfunction "IN/OUT_1") (pintype "bidirectional"))
    )
    (net (code "57") (name "GND") (class "Default")
      (node (ref "C1") (pin "1") (pinfunction "1_1") (pintype "passive"))
      (node (ref "C2") (pin "1") (pinfunction "1_1") (pintype "passive"))
      (node (ref "C3") (pin "-") (pinfunction "-_-") (pintype "passive"))
      (node (ref "C4") (pin "-") (pinfunction "-_-") (pintype "passive"))
      (node (ref "C5") (pin "2") (pinfunction "2_2") (pintype "passive"))
      (node (ref "C6") (pin "2") (pinfunction "2_2") (pintype "passive"))
      (node (ref "C7") (pin "2") (pinfunction "2_2") (pintype "passive"))
      (node (ref "C8") (pin "2") (pinfunction "2_2") (pintype "passive"))
      (node (ref "C9") (pin "2") (pinfunction "2_2") (pintype "passive"))
      (node (ref "GND") (pin "TP") (pinfunction "TP_TP") (pintype "input"))
      (node (ref "LED1") (pin "C") (pinfunction "C_C") (pintype "passive"))
      (node (ref "LED10") (pin "4") (pinfunction "GND_4") (pintype "power_in"))
      (node (ref "LED11") (pin "4") (pinfunction "GND_4") (pintype "power_in"))
      (node (ref "LED4") (pin "4") (pinfunction "GND_4") (pintype "power_in"))
      (node (ref "LED5") (pin "4") (pinfunction "GND_4") (pintype "power_in"))
      (node (ref "LED6") (pin "4") (pinfunction "GND_4") (pintype "power_in"))
      (node (ref "LED7") (pin "4") (pinfunction "GND_4") (pintype "power_in"))
      (node (ref "LED8") (pin "4") (pinfunction "GND_4") (pintype "power_in"))
      (node (ref "LED9") (pin "4") (pinfunction "GND_4") (pintype "power_in"))
      (node (ref "S1") (pin "L2") (pinfunction "P$2_L2") (pintype "bidirectional"))
      (node (ref "S1") (pin "S2") (pinfunction "2_S2") (pintype "passive"))
      (node (ref "S2") (pin "L2") (pinfunction "P$2_L2") (pintype "bidirectional"))
      (node (ref "S2") (pin "S2") (pinfunction "2_S2") (pintype "passive"))
      (node (ref "S3") (pin "L2") (pinfunction "P$2_L2") (pintype "bidirectional"))
      (node (ref "S3") (pin "S2") (pinfunction "2_S2") (pintype "passive"))
      (node (ref "S4") (pin "L2") (pinfunction "P$2_L2") (pintype "bidirectional"))
      (node (ref "S4") (pin "S2") (pinfunction "2_S2") (pintype "passive"))
      (node (ref "S5") (pin "L2") (pinfunction "P$2_L2") (pintype "bidirectional"))
      (node (ref "S5") (pin "S2") (pinfunction "2_S2") (pintype "passive"))
      (node (ref "S6") (pin "L2") (pinfunction "P$2_L2") (pintype "bidirectional"))
      (node (ref "S6") (pin "S2") (pinfunction "2_S2") (pintype "passive"))
      (node (ref "S7") (pin "L2") (pinfunction "P$2_L2") (pintype "bidirectional"))
      (node (ref "S7") (pin "S2") (pinfunction "2_S2") (pintype "passive"))
      (node (ref "S8") (pin "L2") (pinfunction "P$2_L2") (pintype "bidirectional"))
      (node (ref "S8") (pin "S2") (pinfunction "2_S2") (pintype "passive"))
      (node (ref "S9") (pin "3") (pinfunction "3_3") (pintype "passive"))
      (node (ref "S9") (pin "4") (pinfunction "4_4") (pintype "passive"))
      (node (ref "SV3") (pin "1") (pinfunction "1_1") (pintype "passive"))
      (node (ref "SV7") (pin "1") (pinfunction "1_1") (pintype "passive"))
      (node (ref "SV9") (pin "1") (pinfunction "1_1") (pintype "passive"))
      (node (ref "U$2") (pin "C") (pinfunction "C_C") (pintype "bidirectional"))
      (node (ref "U$2") (pin "GND0") (pinfunction "GND_GND0") (pintype "bidirectional"))
      (node (ref "U$2") (pin "GND1") (pinfunction "GND_GND1") (pintype "bidirectional"))
      (node (ref "U$2") (pin "GND2") (pinfunction "GND_GND2") (pintype "bidirectional"))
      (node (ref "U$2") (pin "GND3") (pinfunction "GND_GND3") (pintype "bidirectional"))
      (node (ref "U$3") (pin "C") (pinfunction "C_C") (pintype "bidirectional"))
      (node (ref "U$3") (pin "GND0") (pinfunction "GND_GND0") (pintype "bidirectional"))
      (node (ref "U$3") (pin "GND1") (pinfunction "GND_GND1") (pintype "bidirectional"))
      (node (ref "U$3") (pin "GND2") (pinfunction "GND_GND2") (pintype "bidirectional"))
      (node (ref "U$3") (pin "GND3") (pinfunction "GND_GND3") (pintype "bidirectional"))
      (node (ref "U1") (pin "15") (pinfunction "GND_2_15") (pintype "passive"))
      (node (ref "U1") (pin "23") (pinfunction "GND_3_23") (pintype "passive"))
      (node (ref "U1") (pin "35") (pinfunction "GND_4_35") (pintype "passive"))
      (node (ref "U1") (pin "43") (pinfunction "GND_43") (pintype "passive"))
      (node (ref "U1") (pin "5") (pinfunction "UGND_5") (pintype "passive"))
      (node (ref "U2") (pin "15") (pinfunction "GND_15") (pintype "bidirectional"))
      (node (ref "U2") (pin "23") (pinfunction "GND_23") (pintype "bidirectional"))
      (node (ref "U2") (pin "35") (pinfunction "GND_35") (pintype "bidirectional"))
      (node (ref "U2") (pin "43") (pinfunction "GND_43") (pintype "bidirectional"))
      (node (ref "U2") (pin "5") (pinfunction "UGND_5") (pintype "bidirectional"))
      (node (ref "U2") (pin "TAB") (pinfunction "GND_TAB") (pintype "bidirectional"))
      (node (ref "U3") (pin "2") (pinfunction "GND_2") (pintype "input"))
      (node (ref "USB-MICROB") (pin "5") (pinfunction "5_5") (pintype "passive"))
      (node (ref "USB-MICROB") (pin "S1") (pinfunction "SHIELD_S1") (pintype "passive"))
      (node (ref "USB-MICROB") (pin "S2") (pinfunction "SHIELD_S2") (pintype "passive"))
      (node (ref "USB-MICROB") (pin "S3") (pinfunction "SHIELD_S3") (pintype "passive"))
      (node (ref "USB-MICROB") (pin "S4") (pinfunction "SHIELD_S4") (pintype "passive"))
      (node (ref "USB-MICROB") (pin "S5") (pinfunction "SHIELD_S5") (pintype "passive"))
      (node (ref "USB-MICROB") (pin "S6") (pinfunction "SHIELD_S6") (pintype "passive"))
      (node (ref "USB-TYPEC") (pin "A1") (pinfunction "GND1_A1") (pintype "passive"))
      (node (ref "USB-TYPEC") (pin "A12") (pinfunction "GND2_A12") (pintype "passive"))
      (node (ref "USB-TYPEC") (pin "B1") (pinfunction "GND3_B1") (pintype "passive"))
      (node (ref "USB-TYPEC") (pin "B12") (pinfunction "GND4_B12") (pintype "passive"))
      (node (ref "USB-TYPEC") (pin "S1") (pinfunction "SHIELD_S1") (pintype "passive"))
      (node (ref "USB-TYPEC") (pin "S2") (pinfunction "SHIELD_S2") (pintype "passive"))
      (node (ref "USB-TYPEC") (pin "S3") (pinfunction "SHIELD_S3") (pintype "passive"))
      (node (ref "USB-TYPEC") (pin "S4") (pinfunction "SHIELD_S4") (pintype "passive"))
      (node (ref "Y1") (pin "2") (pinfunction "GND_2") (pintype "power_in"))
      (node (ref "Y1") (pin "4") (pinfunction "GND_4") (pintype "power_in"))
    )
    (net (code "58") (name "Net-(D1-A)") (class "Default")
      (node (ref "D1") (pin "2") (pinfunction "A_2") (pintype "passive"))
      (node (ref "F1") (pin "2") (pinfunction "2_2") (pintype "bidirectional"))
      (node (ref "SJ1") (pin "1") (pinfunction "1_1") (pintype "passive"))
    )
    (net (code "59") (name "Net-(LED1-PadA)") (class "Default")
      (node (ref "LED1") (pin "A") (pinfunction "A_A") (pintype "passive"))
      (node (ref "R3") (pin "1") (pinfunction "1_1") (pintype "passive"))
    )
    (net (code "60") (name "Net-(LED2-PadA)") (class "Default")
      (node (ref "LED2") (pin "A") (pinfunction "A_A") (pintype "passive"))
      (node (ref "R5") (pin "1") (pinfunction "1_1") (pintype "passive"))
    )
    (net (code "61") (name "Net-(LED3-PadA)") (class "Default")
      (node (ref "LED3") (pin "A") (pinfunction "A_A") (pintype "passive"))
      (node (ref "R6") (pin "1") (pinfunction "1_1") (pintype "passive"))
    )
    (net (code "62") (name "Net-(LED4-DO)") (class "Default")
      (node (ref "LED4") (pin "3") (pinfunction "DO_3") (pintype "output"))
      (node (ref "LED5") (pin "1") (pinfunction "DI_1") (pintype "input"))
    )
    (net (code "63") (name "Net-(LED5-DO)") (class "Default")
      (node (ref "LED5") (pin "3") (pinfunction "DO_3") (pintype "output"))
      (node (ref "LED6") (pin "1") (pinfunction "DI_1") (pintype "input"))
    )
    (net (code "64") (name "Net-(LED6-DO)") (class "Default")
      (node (ref "LED6") (pin "3") (pinfunction "DO_3") (pintype "output"))
      (node (ref "LED7") (pin "1") (pinfunction "DI_1") (pintype "input"))
    )
    (net (code "65") (name "Net-(LED8-DO)") (class "Default")
      (node (ref "LED8") (pin "3") (pinfunction "DO_3") (pintype "output"))
      (node (ref "LED9") (pin "1") (pinfunction "DI_1") (pintype "input"))
    )
    (net (code "66") (name "Net-(LED10-DI)") (class "Default")
      (node (ref "LED10") (pin "1") (pinfunction "DI_1") (pintype "input"))
      (node (ref "LED9") (pin "3") (pinfunction "DO_3") (pintype "output"))
    )
    (net (code "67") (name "Net-(LED10-DO)") (class "Default")
      (node (ref "LED10") (pin "3") (pinfunction "DO_3") (pintype "output"))
      (node (ref "LED11") (pin "1") (pinfunction "DI_1") (pintype "input"))
    )
    (net (code "68") (name "Net-(Q1-B)") (class "Default")
      (node (ref "Q1") (pin "1") (pinfunction "B_1") (pintype "passive"))
      (node (ref "R9") (pin "1") (pinfunction "1_1") (pintype "passive"))
    )
    (net (code "69") (name "Net-(Q1-C)") (class "Default")
      (node (ref "Q1") (pin "3") (pinfunction "C_3") (pintype "passive"))
      (node (ref "R10") (pin "2") (pinfunction "2_2") (pintype "passive"))
    )
    (net (code "70") (name "UVCC") (class "Default")
      (node (ref "C8") (pin "1") (pinfunction "1_1") (pintype "passive"))
      (node (ref "F1") (pin "1") (pinfunction "1_1") (pintype "bidirectional"))
      (node (ref "R8") (pin "2") (pinfunction "2_2") (pintype "passive"))
      (node (ref "U1") (pin "2") (pinfunction "UVCC_2") (pintype "power_in"))
      (node (ref "U1") (pin "7") (pinfunction "VBUS_7") (pintype "input"))
      (node (ref "U2") (pin "2") (pinfunction "UVCC_2") (pintype "bidirectional"))
      (node (ref "U2") (pin "7") (pinfunction "VBUS_7") (pintype "bidirectional"))
      (node (ref "USB-MICROB") (pin "1") (pinfunction "1_1") (pintype "passive"))
      (node (ref "USB-TYPEC") (pin "A4") (pinfunction "VBUS1_A4") (pintype "passive"))
      (node (ref "USB-TYPEC") (pin "A9") (pinfunction "VBUS2_A9") (pintype "passive"))
      (node (ref "USB-TYPEC") (pin "B4") (pinfunction "VBUS3_B4") (pintype "passive"))
      (node (ref "USB-TYPEC") (pin "B9") (pinfunction "VBUS4_B9") (pintype "passive"))
      (node (ref "VBUS") (pin "TP") (pinfunction "TP_TP") (pintype "input"))
    )
    (net (code "71") (name "VCC") (class "Default")
      (node (ref "C4") (pin "+") (pinfunction "+_+") (pintype "passive"))
      (node (ref "C5") (pin "1") (pinfunction "1_1") (pintype "passive"))
      (node (ref "C6") (pin "1") (pinfunction "1_1") (pintype "passive"))
      (node (ref "LED2") (pin "C") (pinfunction "C_C") (pintype "passive"))
      (node (ref "LED3") (pin "C") (pinfunction "C_C") (pintype "passive"))
      (node (ref "Q1") (pin "2") (pinfunction "E_2") (pintype "passive"))
      (node (ref "R3") (pin "2") (pinfunction "2_2") (pintype "passive"))
      (node (ref "R4") (pin "2") (pinfunction "2_2") (pintype "passive"))
      (node (ref "R7") (pin "1") (pinfunction "1_1") (pintype "passive"))
      (node (ref "SJ1") (pin "2") (pinfunction "2_2") (pintype "passive"))
      (node (ref "SV9") (pin "5") (pinfunction "5_5") (pintype "passive"))
      (node (ref "U1") (pin "14") (pinfunction "VCC_2_14") (pintype "power_in"))
      (node (ref "U1") (pin "24") (pinfunction "AVCC_2_24") (pintype "power_in"))
      (node (ref "U1") (pin "34") (pinfunction "VCC_34") (pintype "power_in"))
      (node (ref "U1") (pin "44") (pinfunction "AVCC_44") (pintype "power_in"))
      (node (ref "U2") (pin "14") (pinfunction "VCC_14") (pintype "bidirectional"))
      (node (ref "U2") (pin "24") (pinfunction "AVCC_24") (pintype "bidirectional"))
      (node (ref "U2") (pin "34") (pinfunction "VCC_34") (pintype "bidirectional"))
      (node (ref "U2") (pin "44") (pinfunction "AVCC_44") (pintype "bidirectional"))
      (node (ref "U3") (pin "5") (pinfunction "OUT_5") (pintype "passive"))
      (node (ref "VCC") (pin "TP") (pinfunction "TP_TP") (pintype "input"))
    )
    (net (code "72") (name "WSVCC") (class "Default")
      (node (ref "LED10") (pin "2") (pinfunction "VDD_2") (pintype "power_in"))
      (node (ref "LED11") (pin "2") (pinfunction "VDD_2") (pintype "power_in"))
      (node (ref "LED4") (pin "2") (pinfunction "VDD_2") (pintype "power_in"))
      (node (ref "LED5") (pin "2") (pinfunction "VDD_2") (pintype "power_in"))
      (node (ref "LED6") (pin "2") (pinfunction "VDD_2") (pintype "power_in"))
      (node (ref "LED7") (pin "2") (pinfunction "VDD_2") (pintype "power_in"))
      (node (ref "LED8") (pin "2") (pinfunction "VDD_2") (pintype "power_in"))
      (node (ref "LED9") (pin "2") (pinfunction "VDD_2") (pintype "power_in"))
      (node (ref "R7") (pin "2") (pinfunction "2_2") (pintype "passive"))
      (node (ref "R8") (pin "1") (pinfunction "1_1") (pintype "passive"))
      (node (ref "SV2") (pin "1") (pinfunction "1_1") (pintype "passive"))
      (node (ref "SV6") (pin "1") (pinfunction "1_1") (pintype "passive"))
    )
    (net (code "73") (name "unconnected-(U3-BP-Pad4)") (class "Default")
      (node (ref "U3") (pin "4") (pinfunction "BP_4") (pintype "input"))
    )
    (net (code "74") (name "unconnected-(USB-MICROB-Pad4)") (class "Default")
      (node (ref "USB-MICROB") (pin "4") (pinfunction "4_4") (pintype "passive"))
    )
    (net (code "75") (name "unconnected-(USB-TYPEC-CC1-PadA5)") (class "Default")
      (node (ref "USB-TYPEC") (pin "A5") (pinfunction "CC1_A5") (pintype "passive"))
    )
    (net (code "76") (name "unconnected-(USB-TYPEC-CC2-PadB5)") (class "Default")
      (node (ref "USB-TYPEC") (pin "B5") (pinfunction "CC2_B5") (pintype "passive"))
    )
    (net (code "77") (name "unconnected-(USB-TYPEC-RX1+-PadB11)") (class "Default")
      (node (ref "USB-TYPEC") (pin "B11") (pinfunction "RX1+_B11") (pintype "passive"))
    )
    (net (code "78") (name "unconnected-(USB-TYPEC-RX1--PadB10)") (class "Default")
      (node (ref "USB-TYPEC") (pin "B10") (pinfunction "RX1-_B10") (pintype "passive"))
    )
    (net (code "79") (name "unconnected-(USB-TYPEC-RX2+-PadA11)") (class "Default")
      (node (ref "USB-TYPEC") (pin "A11") (pinfunction "RX2+_A11") (pintype "passive"))
    )
    (net (code "80") (name "unconnected-(USB-TYPEC-RX2--PadA10)") (class "Default")
      (node (ref "USB-TYPEC") (pin "A10") (pinfunction "RX2-_A10") (pintype "passive"))
    )
    (net (code "81") (name "unconnected-(USB-TYPEC-SBU1-PadA8)") (class "Default")
      (node (ref "USB-TYPEC") (pin "A8") (pinfunction "SBU1_A8") (pintype "passive"))
    )
    (net (code "82") (name "unconnected-(USB-TYPEC-SBU2-PadB8)") (class "Default")
      (node (ref "USB-TYPEC") (pin "B8") (pinfunction "SBU2_B8") (pintype "passive"))
    )
    (net (code "83") (name "unconnected-(USB-TYPEC-TX1+-PadA2)") (class "Default")
      (node (ref "USB-TYPEC") (pin "A2") (pinfunction "TX1+_A2") (pintype "passive"))
    )
    (net (code "84") (name "unconnected-(USB-TYPEC-TX1--PadA3)") (class "Default")
      (node (ref "USB-TYPEC") (pin "A3") (pinfunction "TX1-_A3") (pintype "passive"))
    )
    (net (code "85") (name "unconnected-(USB-TYPEC-TX2+-PadB2)") (class "Default")
      (node (ref "USB-TYPEC") (pin "B2") (pinfunction "TX2+_B2") (pintype "passive"))
    )
    (net (code "86") (name "unconnected-(USB-TYPEC-TX2--PadB3)") (class "Default")
      (node (ref "USB-TYPEC") (pin "B3") (pinfunction "TX2-_B3") (pintype "passive"))
    )
  )
)
